# backplane_main.net
KiCad netlist of a schematic drawn in Altium Designer
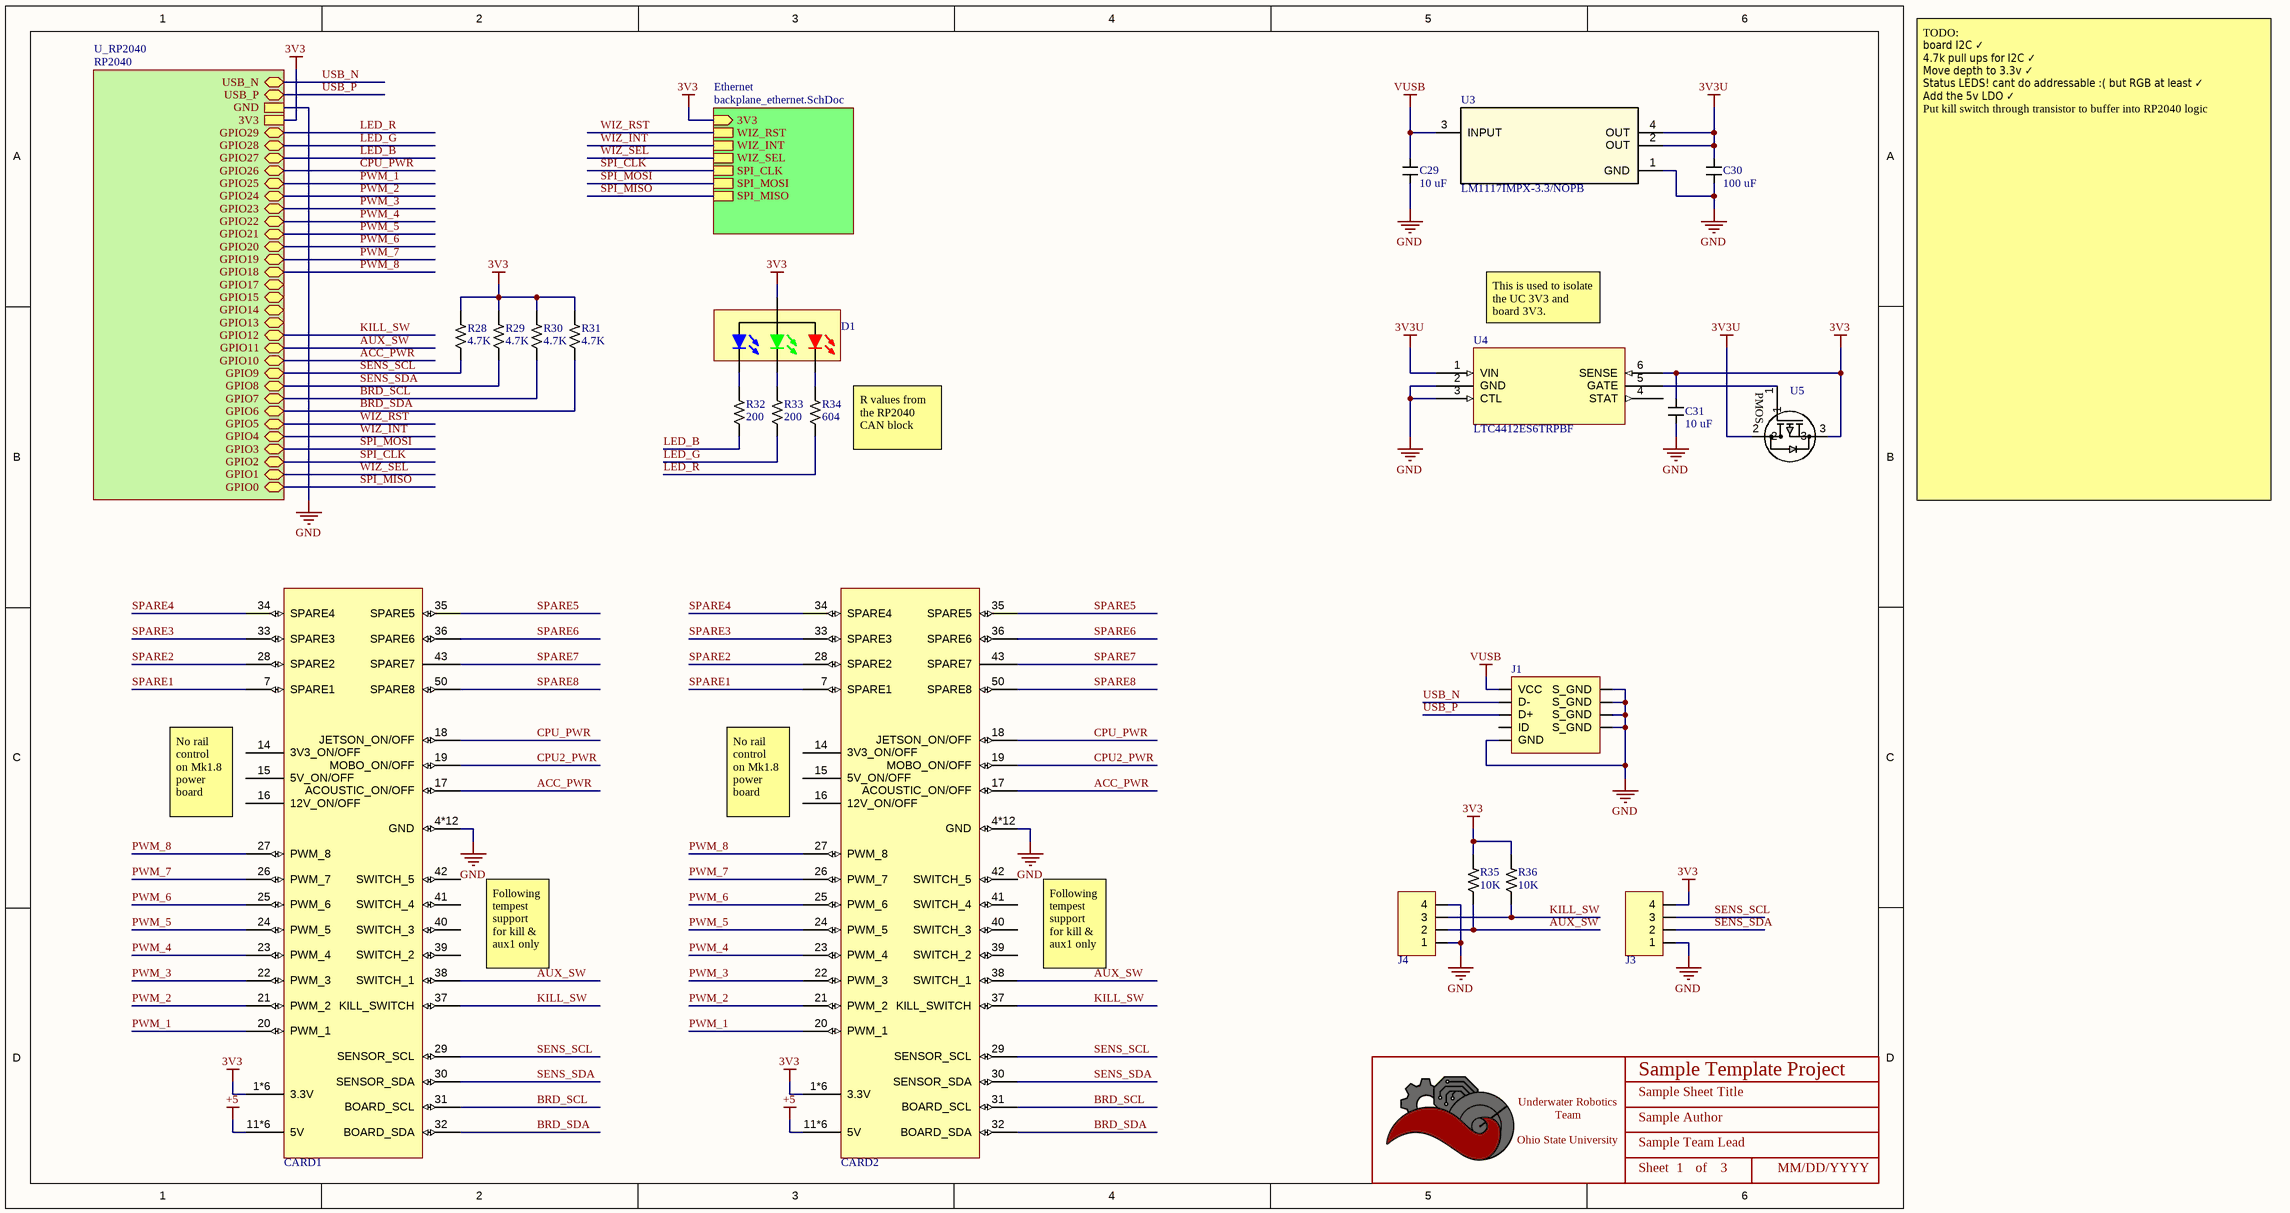
[diagram p0: backplane_main.SchDoc]

(export (version "E")
  (design (tool "Eeschema 10.0.6"))
  (components
    (comp (ref "*")
      (value "Title_Block")
      (footprint "LOGO")
      (description "UWRT Schematic Title Block Template\r\n\r\nCreated June 2021, Dylan Trainor")
      (libsource (lib "UWRT") (part "Title_Block"))
    )
    (comp (ref "C29")
      (value "10uF Ceramic 6.3V")
      (footprint "CAPACITOR_0603")
      (description "Cap 10uF 6.3V +/-20%\r\nCeramic 0603")
      (fields
        (field (name "TOLERANCE") "+/- 20%")
        (field (name "VOLTAGE") "6.3V")
        (field (name "VALUE (UF)") "10 uF")
        (field (name "MADE BY") "Flip B")
      )
      (libsource (lib "Capacitors") (part "CAPACITOR_10uF_0603"))
    )
    (comp (ref "C30")
      (value "100uF Ceramic 6.3V")
      (footprint "CAPACITOR_0603")
      (description "Cap 100uF 6.3V +/-20%\r\nCeramic 0603")
      (fields
        (field (name "TOLERANCE") "+/- 20%")
        (field (name "VOLTAGE") "6.3V")
        (field (name "VALUE (UF)") "100 uF")
        (field (name "MADE BY") "Dylan Trainor")
      )
      (libsource (lib "Capacitors") (part "CAPACITOR_100uF_0603"))
    )
    (comp (ref "C31")
      (value "10uF Ceramic 6.3V")
      (footprint "CAPACITOR_0603")
      (description "Cap 10uF 6.3V +/-20%\r\nCeramic 0603")
      (fields
        (field (name "TOLERANCE") "+/- 20%")
        (field (name "VOLTAGE") "6.3V")
        (field (name "VALUE (UF)") "10 uF")
        (field (name "MADE BY") "Flip B")
      )
      (libsource (lib "Capacitors") (part "CAPACITOR_10uF_0603"))
    )
    (comp (ref "CARD1")
      (value "BACKPLANE_EDGE_SOCKET")
      (footprint "SOCKET_BACKPLANE_EDGE_CONN")
      (description "Backplane Edge Socket")
      (fields (field (name "MADE BY") "Robert Pafford"))
      (libsource (lib "Connectors") (part "BACKPLANE_EDGE_SOCKET"))
    )
    (comp (ref "CARD2")
      (value "BACKPLANE_EDGE_SOCKET")
      (footprint "SOCKET_BACKPLANE_EDGE_CONN")
      (description "Backplane Edge Socket")
      (fields (field (name "MADE BY") "Robert Pafford"))
      (libsource (lib "Connectors") (part "BACKPLANE_EDGE_SOCKET"))
    )
    (comp (ref "D1")
      (value "EAST1616RGBB4")
      (footprint "LED_0606_4SMD")
      (description "LED RGB CLEAR 4SMD")
      (fields (field (name "MADE BY") "Robert Pafford"))
      (libsource (lib "Diodes") (part "LED_RGB_4SMD"))
    )
    (comp (ref "J1")
      (value "USB_MICRO R/A")
      (footprint "CONN_MINIUSB")
      (description "Amphenol Micro USB-B\r\nUSB2.0 5 Pin Right Angle SMD")
      (fields (field (name "MANUFACTURER") "Amphenol") (field (name "CREATED BY") "Flip B"))
      (libsource (lib "Connectors") (part "CONN_MICROUSB"))
    )
    (comp (ref "J3")
      (value "4 POS R/A")
      (footprint "CONN_MOLEX_MINIFIT JR_4 POS_R/A")
      (description "Molex Minifit Jr. 5569 \r\n4 Pos R/A Natural")
      (fields (field (name "MANUFACTURER") "Molex") (field (name "CREATED BY") "Flip B"))
      (libsource (lib "Connectors") (part "CONN_MOLEX_MINIFIT JR_4POS_R/A"))
    )
    (comp (ref "J4")
      (value "4 POS R/A")
      (footprint "CONN_MOLEX_MINIFIT JR_4 POS_R/A")
      (description "Molex Minifit Jr. 5569 \r\n4 Pos R/A Natural")
      (fields (field (name "MANUFACTURER") "Molex") (field (name "CREATED BY") "Flip B"))
      (libsource (lib "Connectors") (part "CONN_MOLEX_MINIFIT JR_4POS_R/A"))
    )
    (comp (ref "R28")
      (value "10k Ohm 5% 1/10W")
      (footprint "RESISTOR_0603")
      (description "RES 10k OHM 5% 1/10W 0603")
      (fields
        (field (name "TOLERANCE") "+/- 5%")
        (field (name "VALUE  (OHMS)") "4.7K")
        (field (name "MADE BY") "Robert Pafford")
      )
      (libsource (lib "Resistors") (part "RESISTOR_10K_0603"))
    )
    (comp (ref "R29")
      (value "10k Ohm 5% 1/10W")
      (footprint "RESISTOR_0603")
      (description "RES 10k OHM 5% 1/10W 0603")
      (fields
        (field (name "TOLERANCE") "+/- 5%")
        (field (name "VALUE  (OHMS)") "4.7K")
        (field (name "MADE BY") "Robert Pafford")
      )
      (libsource (lib "Resistors") (part "RESISTOR_10K_0603"))
    )
    (comp (ref "R30")
      (value "10k Ohm 5% 1/10W")
      (footprint "RESISTOR_0603")
      (description "RES 10k OHM 5% 1/10W 0603")
      (fields
        (field (name "TOLERANCE") "+/- 5%")
        (field (name "VALUE  (OHMS)") "4.7K")
        (field (name "MADE BY") "Robert Pafford")
      )
      (libsource (lib "Resistors") (part "RESISTOR_10K_0603"))
    )
    (comp (ref "R31")
      (value "10k Ohm 5% 1/10W")
      (footprint "RESISTOR_0603")
      (description "RES 10k OHM 5% 1/10W 0603")
      (fields
        (field (name "TOLERANCE") "+/- 5%")
        (field (name "VALUE  (OHMS)") "4.7K")
        (field (name "MADE BY") "Robert Pafford")
      )
      (libsource (lib "Resistors") (part "RESISTOR_10K_0603"))
    )
    (comp (ref "R32")
      (value "10k Ohm 5% 1/10W")
      (footprint "RESISTOR_0603")
      (description "RES 10k OHM 5% 1/10W 0603")
      (fields
        (field (name "TOLERANCE") "+/- 5%")
        (field (name "VALUE  (OHMS)") "200")
        (field (name "MADE BY") "Robert Pafford")
      )
      (libsource (lib "Resistors") (part "RESISTOR_10K_0603"))
    )
    (comp (ref "R33")
      (value "10k Ohm 5% 1/10W")
      (footprint "RESISTOR_0603")
      (description "RES 10k OHM 5% 1/10W 0603")
      (fields
        (field (name "TOLERANCE") "+/- 5%")
        (field (name "VALUE  (OHMS)") "200")
        (field (name "MADE BY") "Robert Pafford")
      )
      (libsource (lib "Resistors") (part "RESISTOR_10K_0603"))
    )
    (comp (ref "R34")
      (value "10k Ohm 5% 1/10W")
      (footprint "RESISTOR_0603")
      (description "RES 10k OHM 5% 1/10W 0603")
      (fields
        (field (name "TOLERANCE") "+/- 5%")
        (field (name "VALUE  (OHMS)") "604")
        (field (name "MADE BY") "Robert Pafford")
      )
      (libsource (lib "Resistors") (part "RESISTOR_10K_0603"))
    )
    (comp (ref "R35")
      (value "10k Ohm 5% 1/10W")
      (footprint "RESISTOR_0603")
      (description "RES 10k OHM 5% 1/10W 0603")
      (fields
        (field (name "TOLERANCE") "+/- 5%")
        (field (name "VALUE  (OHMS)") "10K")
        (field (name "MADE BY") "Robert Pafford")
      )
      (libsource (lib "Resistors") (part "RESISTOR_10K_0603"))
    )
    (comp (ref "R36")
      (value "10k Ohm 5% 1/10W")
      (footprint "RESISTOR_0603")
      (description "RES 10k OHM 5% 1/10W 0603")
      (fields
        (field (name "TOLERANCE") "+/- 5%")
        (field (name "VALUE  (OHMS)") "10K")
        (field (name "MADE BY") "Robert Pafford")
      )
      (libsource (lib "Resistors") (part "RESISTOR_10K_0603"))
    )
    (comp (ref "U3")
      (value "LM1117IMPX-3.3/NOPB")
      (footprint "SOT-223-4")
      (description "IC REG LIN 3.3V 800MA SOT223-4")
      (fields
        (field (name "PARTNUMBER") "LM1117IMP-3.3/NOPB")
        (field (name "MANUFACTURER") "Texas Instruments")
        (field (name "CREATED BY") "Dylan T")
      )
      (libsource (lib "Converter") (part "LM1117IMPX-3.3/NOPB"))
    )
    (comp (ref "U4")
      (value "LTC4412ES6TRPBF")
      (footprint "Integrated Circuits:TSOT-23_S6")
      (description "OR Controller Source Selector Switch P-Channel 2:1 TSOT-23-6")
      (fields (field (name "MP") "LTC4412ES6#TRPBF") (field (name "MF") "Analog Devices"))
      (libsource (lib "Integrated Circuits") (part "LTC4412ES6TRPBF"))
    )
    (comp (ref "U5")
      (value "MOSFET P-CHANNEL 20V 4.7A SOT23")
      (footprint "SOT-23-3")
      (description "P-Channel 20 V 4.7A (Tc) 1.56W (Tc) Surface Mount SOT-23")
      (fields
        (field (name "MANUFACTURER_PART_NUMBER") "TSM500P02CX")
        (field (name "CREATED BY") "Robert Pafford")
      )
      (libsource (lib "Transistors") (part "TSM500P02CX"))
    )
  )
  (nets
    (net (code "1") (name "+5") (class "Default")
      (node (ref "CARD1") (pin "11*6") (pinfunction "5V_11*6") (pintype "power_in"))
      (node (ref "CARD2") (pin "11*6") (pinfunction "5V_11*6") (pintype "power_in"))
    )
    (net (code "2") (name "/ACC_PWR") (class "Default")
      (node (ref "CARD1") (pin "17") (pinfunction "ACOUSTIC_ON/OFF_17") (pintype "bidirectional"))
      (node (ref "CARD2") (pin "17") (pinfunction "ACOUSTIC_ON/OFF_17") (pintype "bidirectional"))
    )
    (net (code "3") (name "/AUX_SW") (class "Default")
      (node (ref "CARD1") (pin "38") (pinfunction "SWITCH_1_38") (pintype "bidirectional"))
      (node (ref "CARD2") (pin "38") (pinfunction "SWITCH_1_38") (pintype "bidirectional"))
      (node (ref "J4") (pin "2") (pinfunction "2_2") (pintype "passive"))
      (node (ref "R35") (pin "2") (pinfunction "2_2") (pintype "passive"))
    )
    (net (code "4") (name "/BRD_SCL") (class "Default")
      (node (ref "CARD1") (pin "31") (pinfunction "BOARD_SCL_31") (pintype "bidirectional"))
      (node (ref "CARD2") (pin "31") (pinfunction "BOARD_SCL_31") (pintype "bidirectional"))
      (node (ref "R30") (pin "2") (pinfunction "2_2") (pintype "passive"))
    )
    (net (code "5") (name "/BRD_SDA") (class "Default")
      (node (ref "CARD1") (pin "32") (pinfunction "BOARD_SDA_32") (pintype "bidirectional"))
      (node (ref "CARD2") (pin "32") (pinfunction "BOARD_SDA_32") (pintype "bidirectional"))
      (node (ref "R31") (pin "2") (pinfunction "2_2") (pintype "passive"))
    )
    (net (code "6") (name "/CPU2_PWR") (class "Default")
      (node (ref "CARD1") (pin "19") (pinfunction "MOBO_ON/OFF_19") (pintype "bidirectional"))
      (node (ref "CARD2") (pin "19") (pinfunction "MOBO_ON/OFF_19") (pintype "bidirectional"))
    )
    (net (code "7") (name "/CPU_PWR") (class "Default")
      (node (ref "CARD1") (pin "18") (pinfunction "JETSON_ON/OFF_18") (pintype "bidirectional"))
      (node (ref "CARD2") (pin "18") (pinfunction "JETSON_ON/OFF_18") (pintype "bidirectional"))
    )
    (net (code "12") (name "/KILL_SW") (class "Default")
      (node (ref "CARD1") (pin "37") (pinfunction "KILL_SWITCH_37") (pintype "bidirectional"))
      (node (ref "CARD2") (pin "37") (pinfunction "KILL_SWITCH_37") (pintype "bidirectional"))
      (node (ref "J4") (pin "3") (pinfunction "3_3") (pintype "passive"))
      (node (ref "R36") (pin "2") (pinfunction "2_2") (pintype "passive"))
    )
    (net (code "13") (name "/LED_B") (class "Default")
      (node (ref "R32") (pin "2") (pinfunction "2_2") (pintype "passive"))
    )
    (net (code "14") (name "/LED_G") (class "Default")
      (node (ref "R33") (pin "2") (pinfunction "2_2") (pintype "passive"))
    )
    (net (code "15") (name "/LED_R") (class "Default")
      (node (ref "R34") (pin "2") (pinfunction "2_2") (pintype "passive"))
    )
    (net (code "16") (name "/PWM_1") (class "Default")
      (node (ref "CARD1") (pin "20") (pinfunction "PWM_1_20") (pintype "bidirectional"))
      (node (ref "CARD2") (pin "20") (pinfunction "PWM_1_20") (pintype "bidirectional"))
    )
    (net (code "17") (name "/PWM_2") (class "Default")
      (node (ref "CARD1") (pin "21") (pinfunction "PWM_2_21") (pintype "bidirectional"))
      (node (ref "CARD2") (pin "21") (pinfunction "PWM_2_21") (pintype "bidirectional"))
    )
    (net (code "18") (name "/PWM_3") (class "Default")
      (node (ref "CARD1") (pin "22") (pinfunction "PWM_3_22") (pintype "bidirectional"))
      (node (ref "CARD2") (pin "22") (pinfunction "PWM_3_22") (pintype "bidirectional"))
    )
    (net (code "19") (name "/PWM_4") (class "Default")
      (node (ref "CARD1") (pin "23") (pinfunction "PWM_4_23") (pintype "bidirectional"))
      (node (ref "CARD2") (pin "23") (pinfunction "PWM_4_23") (pintype "bidirectional"))
    )
    (net (code "20") (name "/PWM_5") (class "Default")
      (node (ref "CARD1") (pin "24") (pinfunction "PWM_5_24") (pintype "bidirectional"))
      (node (ref "CARD2") (pin "24") (pinfunction "PWM_5_24") (pintype "bidirectional"))
    )
    (net (code "21") (name "/PWM_6") (class "Default")
      (node (ref "CARD1") (pin "25") (pinfunction "PWM_6_25") (pintype "bidirectional"))
      (node (ref "CARD2") (pin "25") (pinfunction "PWM_6_25") (pintype "bidirectional"))
    )
    (net (code "22") (name "/PWM_7") (class "Default")
      (node (ref "CARD1") (pin "26") (pinfunction "PWM_7_26") (pintype "bidirectional"))
      (node (ref "CARD2") (pin "26") (pinfunction "PWM_7_26") (pintype "bidirectional"))
    )
    (net (code "23") (name "/PWM_8") (class "Default")
      (node (ref "CARD1") (pin "27") (pinfunction "PWM_8_27") (pintype "bidirectional"))
      (node (ref "CARD2") (pin "27") (pinfunction "PWM_8_27") (pintype "bidirectional"))
    )
    (net (code "24") (name "/SENS_SCL") (class "Default")
      (node (ref "CARD1") (pin "29") (pinfunction "SENSOR_SCL_29") (pintype "bidirectional"))
      (node (ref "CARD2") (pin "29") (pinfunction "SENSOR_SCL_29") (pintype "bidirectional"))
      (node (ref "J3") (pin "3") (pinfunction "3_3") (pintype "passive"))
      (node (ref "R28") (pin "2") (pinfunction "2_2") (pintype "passive"))
    )
    (net (code "25") (name "/SENS_SDA") (class "Default")
      (node (ref "CARD1") (pin "30") (pinfunction "SENSOR_SDA_30") (pintype "bidirectional"))
      (node (ref "CARD2") (pin "30") (pinfunction "SENSOR_SDA_30") (pintype "bidirectional"))
      (node (ref "J3") (pin "2") (pinfunction "2_2") (pintype "passive"))
      (node (ref "R29") (pin "2") (pinfunction "2_2") (pintype "passive"))
    )
    (net (code "26") (name "/SPARE1") (class "Default")
      (node (ref "CARD1") (pin "7") (pinfunction "SPARE1_7") (pintype "bidirectional"))
      (node (ref "CARD2") (pin "7") (pinfunction "SPARE1_7") (pintype "bidirectional"))
    )
    (net (code "27") (name "/SPARE2") (class "Default")
      (node (ref "CARD1") (pin "28") (pinfunction "SPARE2_28") (pintype "bidirectional"))
      (node (ref "CARD2") (pin "28") (pinfunction "SPARE2_28") (pintype "bidirectional"))
    )
    (net (code "28") (name "/SPARE3") (class "Default")
      (node (ref "CARD1") (pin "33") (pinfunction "SPARE3_33") (pintype "bidirectional"))
      (node (ref "CARD2") (pin "33") (pinfunction "SPARE3_33") (pintype "bidirectional"))
    )
    (net (code "29") (name "/SPARE4") (class "Default")
      (node (ref "CARD1") (pin "34") (pinfunction "SPARE4_34") (pintype "bidirectional"))
      (node (ref "CARD2") (pin "34") (pinfunction "SPARE4_34") (pintype "bidirectional"))
    )
    (net (code "30") (name "/SPARE5") (class "Default")
      (node (ref "CARD1") (pin "35") (pinfunction "SPARE5_35") (pintype "bidirectional"))
      (node (ref "CARD2") (pin "35") (pinfunction "SPARE5_35") (pintype "bidirectional"))
    )
    (net (code "31") (name "/SPARE6") (class "Default")
      (node (ref "CARD1") (pin "36") (pinfunction "SPARE6_36") (pintype "bidirectional"))
      (node (ref "CARD2") (pin "36") (pinfunction "SPARE6_36") (pintype "bidirectional"))
    )
    (net (code "32") (name "/SPARE7") (class "Default")
      (node (ref "CARD1") (pin "43") (pinfunction "SPARE7_43") (pintype "power_in"))
      (node (ref "CARD2") (pin "43") (pinfunction "SPARE7_43") (pintype "power_in"))
    )
    (net (code "33") (name "/SPARE8") (class "Default")
      (node (ref "CARD1") (pin "50") (pinfunction "SPARE8_50") (pintype "bidirectional"))
      (node (ref "CARD2") (pin "50") (pinfunction "SPARE8_50") (pintype "bidirectional"))
    )
    (net (code "37") (name "/USB_N") (class "Default")
      (node (ref "J1") (pin "2") (pinfunction "D-_2") (pintype "passive"))
    )
    (net (code "38") (name "/USB_P") (class "Default")
      (node (ref "J1") (pin "3") (pinfunction "D+_3") (pintype "passive"))
    )
    (net (code "42") (name "3V3") (class "Default")
      (node (ref "C31") (pin "1") (pinfunction "1_1") (pintype "passive"))
      (node (ref "CARD1") (pin "1*6") (pinfunction "3.3V_1*6") (pintype "power_in"))
      (node (ref "CARD2") (pin "1*6") (pinfunction "3.3V_1*6") (pintype "power_in"))
      (node (ref "D1") (pin "4") (pinfunction "4_4") (pintype "passive"))
      (node (ref "J3") (pin "4") (pinfunction "4_4") (pintype "passive"))
      (node (ref "R28") (pin "1") (pinfunction "1_1") (pintype "passive"))
      (node (ref "R29") (pin "1") (pinfunction "1_1") (pintype "passive"))
      (node (ref "R30") (pin "1") (pinfunction "1_1") (pintype "passive"))
      (node (ref "R31") (pin "1") (pinfunction "1_1") (pintype "passive"))
      (node (ref "R35") (pin "1") (pinfunction "1_1") (pintype "passive"))
      (node (ref "R36") (pin "1") (pinfunction "1_1") (pintype "passive"))
      (node (ref "U4") (pin "6") (pinfunction "SENSE_6") (pintype "input"))
      (node (ref "U5") (pin "3") (pinfunction "3_3") (pintype "passive"))
    )
    (net (code "43") (name "3V3U") (class "Default")
      (node (ref "C30") (pin "1") (pinfunction "1_1") (pintype "passive"))
      (node (ref "U3") (pin "2") (pinfunction "OUT_2") (pintype "power_in"))
      (node (ref "U3") (pin "4") (pinfunction "OUT_4") (pintype "power_in"))
      (node (ref "U4") (pin "1") (pinfunction "VIN_1") (pintype "input"))
      (node (ref "U5") (pin "2") (pinfunction "2_2") (pintype "passive"))
    )
    (net (code "44") (name "GND") (class "Default")
      (node (ref "C29") (pin "2") (pinfunction "2_2") (pintype "passive"))
      (node (ref "C30") (pin "2") (pinfunction "2_2") (pintype "passive"))
      (node (ref "C31") (pin "2") (pinfunction "2_2") (pintype "passive"))
      (node (ref "CARD1") (pin "4*12") (pinfunction "GND_4*12") (pintype "bidirectional"))
      (node (ref "CARD2") (pin "4*12") (pinfunction "GND_4*12") (pintype "bidirectional"))
      (node (ref "J1") (pin "5") (pinfunction "GND_5") (pintype "passive"))
      (node (ref "J1") (pin "6") (pinfunction "S_GND_6") (pintype "passive"))
      (node (ref "J1") (pin "7") (pinfunction "S_GND_7") (pintype "passive"))
      (node (ref "J1") (pin "8") (pinfunction "S_GND_8") (pintype "passive"))
      (node (ref "J1") (pin "9") (pinfunction "S_GND_9") (pintype "passive"))
      (node (ref "J3") (pin "1") (pinfunction "1_1") (pintype "passive"))
      (node (ref "J4") (pin "1") (pinfunction "1_1") (pintype "passive"))
      (node (ref "J4") (pin "4") (pinfunction "4_4") (pintype "passive"))
      (node (ref "U3") (pin "1") (pinfunction "GND_1") (pintype "power_in"))
      (node (ref "U4") (pin "2") (pinfunction "GND_2") (pintype "power_in"))
      (node (ref "U4") (pin "3") (pinfunction "CTL_3") (pintype "input"))
    )
    (net (code "45") (name "Net-(D1-32)") (class "Default")
      (node (ref "D1") (pin "3") (pinfunction "32_3") (pintype "passive"))
      (node (ref "R32") (pin "1") (pinfunction "1_1") (pintype "passive"))
    )
    (net (code "46") (name "Net-(D1-Pad1)") (class "Default")
      (node (ref "D1") (pin "1") (pinfunction "1_1") (pintype "passive"))
      (node (ref "R34") (pin "1") (pinfunction "1_1") (pintype "passive"))
    )
    (net (code "47") (name "Net-(D1-Pad2)") (class "Default")
      (node (ref "D1") (pin "2") (pinfunction "2_2") (pintype "passive"))
      (node (ref "R33") (pin "1") (pinfunction "1_1") (pintype "passive"))
    )
    (net (code "48") (name "Net-(U4-GATE)") (class "Default")
      (node (ref "U4") (pin "5") (pinfunction "GATE_5") (pintype "passive"))
      (node (ref "U5") (pin "1") (pinfunction "1_1") (pintype "passive"))
    )
    (net (code "49") (name "VUSB") (class "Default")
      (node (ref "C29") (pin "1") (pinfunction "1_1") (pintype "passive"))
      (node (ref "J1") (pin "1") (pinfunction "VCC_1") (pintype "passive"))
      (node (ref "U3") (pin "3") (pinfunction "INPUT_3") (pintype "power_in"))
    )
    (net (code "50") (name "unconnected-(CARD1-3V3_ON{slash}OFF-Pad14)") (class "Default")
      (node (ref "CARD1") (pin "14") (pinfunction "3V3_ON/OFF_14") (pintype "power_in"))
    )
    (net (code "51") (name "unconnected-(CARD1-5V_ON{slash}OFF-Pad15)") (class "Default")
      (node (ref "CARD1") (pin "15") (pinfunction "5V_ON/OFF_15") (pintype "power_in"))
    )
    (net (code "52") (name "unconnected-(CARD1-12V_ON{slash}OFF-Pad16)") (class "Default")
      (node (ref "CARD1") (pin "16") (pinfunction "12V_ON/OFF_16") (pintype "power_in"))
    )
    (net (code "53") (name "unconnected-(CARD1-SWITCH_2-Pad39)") (class "Default")
      (node (ref "CARD1") (pin "39") (pinfunction "SWITCH_2_39") (pintype "bidirectional"))
    )
    (net (code "54") (name "unconnected-(CARD1-SWITCH_3-Pad40)") (class "Default")
      (node (ref "CARD1") (pin "40") (pinfunction "SWITCH_3_40") (pintype "bidirectional"))
    )
    (net (code "55") (name "unconnected-(CARD1-SWITCH_4-Pad41)") (class "Default")
      (node (ref "CARD1") (pin "41") (pinfunction "SWITCH_4_41") (pintype "bidirectional"))
    )
    (net (code "56") (name "unconnected-(CARD1-SWITCH_5-Pad42)") (class "Default")
      (node (ref "CARD1") (pin "42") (pinfunction "SWITCH_5_42") (pintype "bidirectional"))
    )
    (net (code "57") (name "unconnected-(CARD2-3V3_ON{slash}OFF-Pad14)") (class "Default")
      (node (ref "CARD2") (pin "14") (pinfunction "3V3_ON/OFF_14") (pintype "power_in"))
    )
    (net (code "58") (name "unconnected-(CARD2-5V_ON{slash}OFF-Pad15)") (class "Default")
      (node (ref "CARD2") (pin "15") (pinfunction "5V_ON/OFF_15") (pintype "power_in"))
    )
    (net (code "59") (name "unconnected-(CARD2-12V_ON{slash}OFF-Pad16)") (class "Default")
      (node (ref "CARD2") (pin "16") (pinfunction "12V_ON/OFF_16") (pintype "power_in"))
    )
    (net (code "60") (name "unconnected-(CARD2-SWITCH_2-Pad39)") (class "Default")
      (node (ref "CARD2") (pin "39") (pinfunction "SWITCH_2_39") (pintype "bidirectional"))
    )
    (net (code "61") (name "unconnected-(CARD2-SWITCH_3-Pad40)") (class "Default")
      (node (ref "CARD2") (pin "40") (pinfunction "SWITCH_3_40") (pintype "bidirectional"))
    )
    (net (code "62") (name "unconnected-(CARD2-SWITCH_4-Pad41)") (class "Default")
      (node (ref "CARD2") (pin "41") (pinfunction "SWITCH_4_41") (pintype "bidirectional"))
    )
    (net (code "63") (name "unconnected-(CARD2-SWITCH_5-Pad42)") (class "Default")
      (node (ref "CARD2") (pin "42") (pinfunction "SWITCH_5_42") (pintype "bidirectional"))
    )
    (net (code "64") (name "unconnected-(J1-ID-Pad4)") (class "Default")
      (node (ref "J1") (pin "4") (pinfunction "ID_4") (pintype "passive"))
    )
    (net (code "65") (name "unconnected-(U4-STAT-Pad4)") (class "Default")
      (node (ref "U4") (pin "4") (pinfunction "STAT_4") (pintype "output"))
    )
  )
)
